# LampenSteuerung_PWM.net
KiCad netlist of a schematic drawn in EAGLE
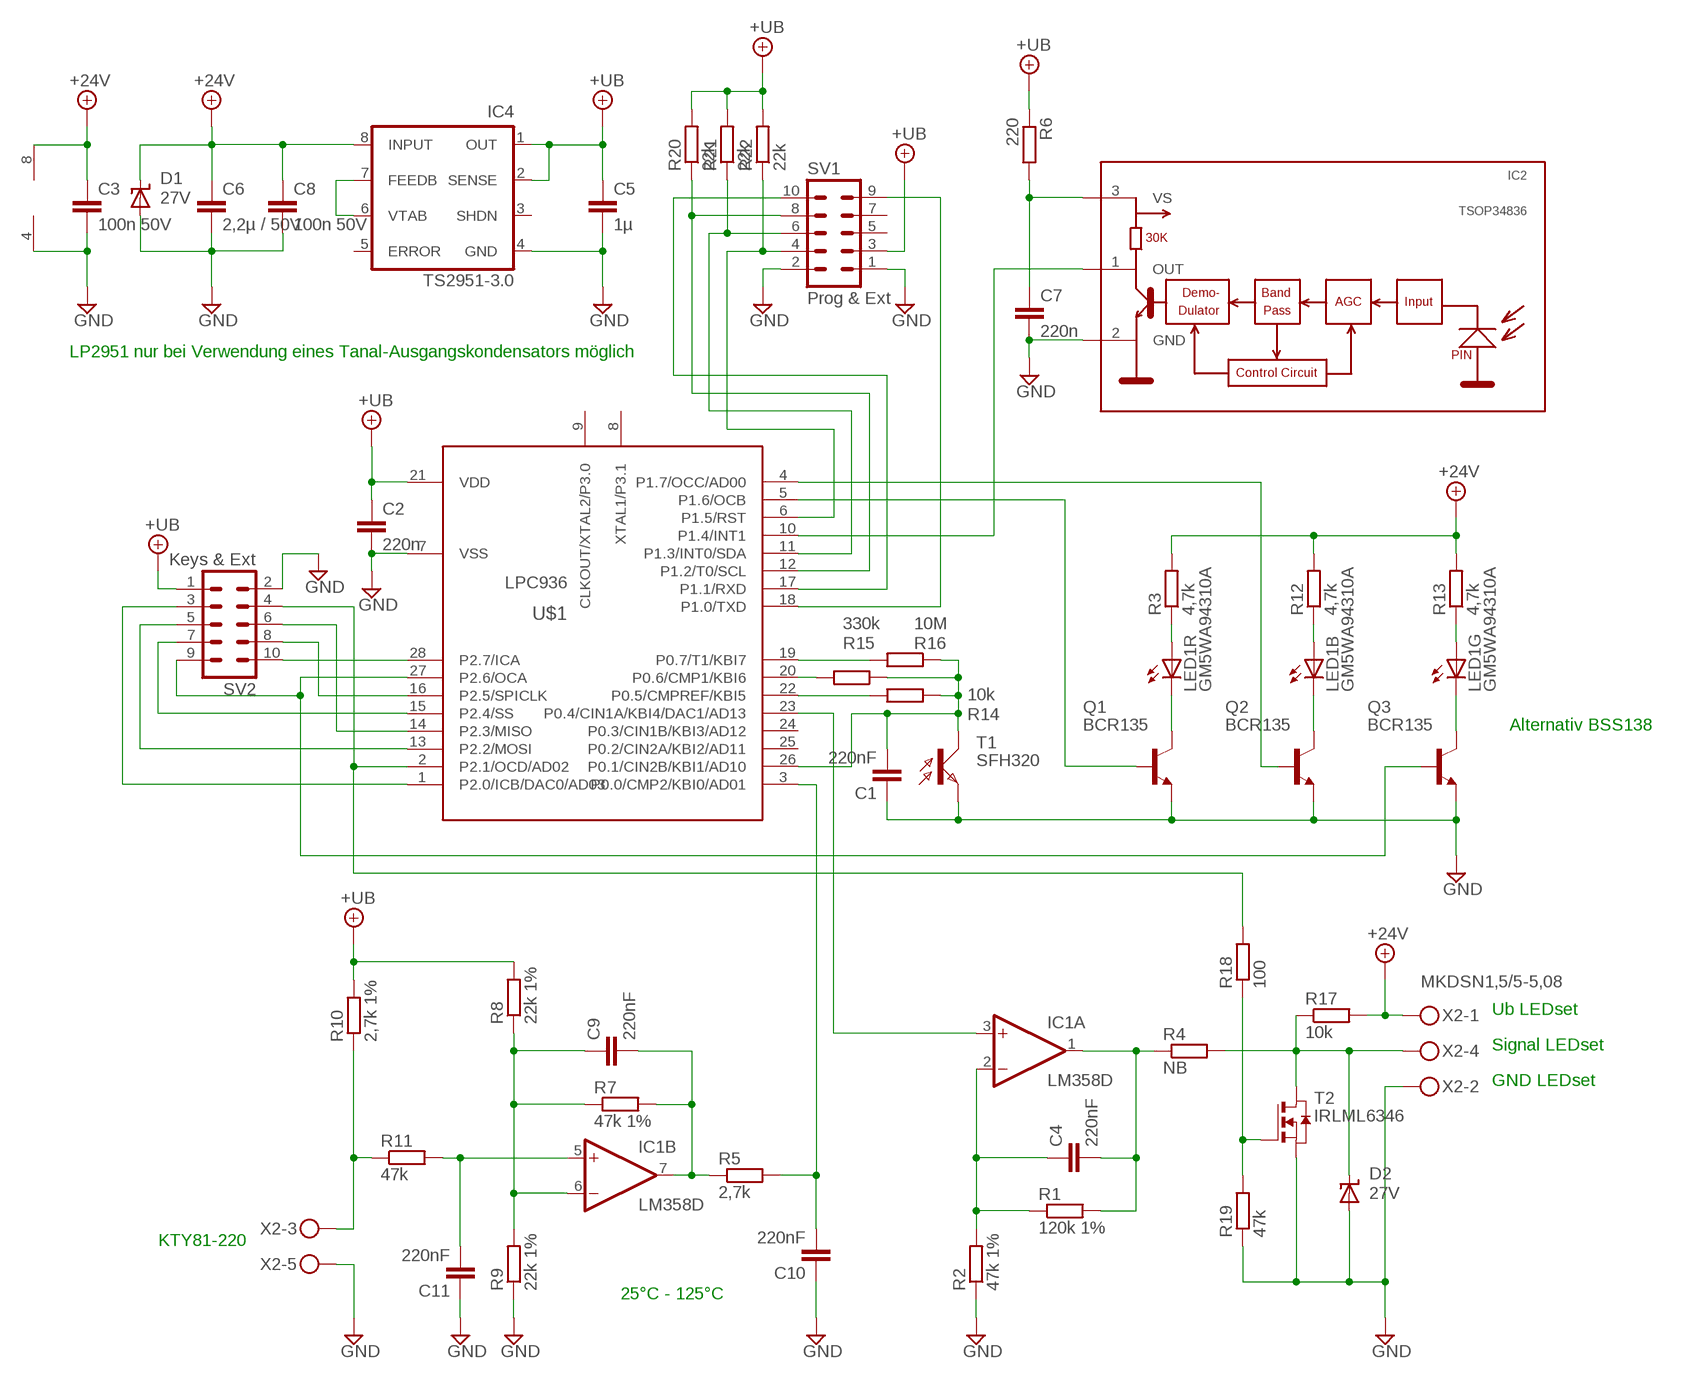
[diagram p0: schematic, sheet 1]

(export (version "E")
  (design (tool "Eeschema 10.0.6"))
  (components
    (comp (ref "C1")
      (value "220nF")
      (footprint "eagle-import:C0603")
      (libsource (lib "eagle-import") (part "C-EUC0603"))
    )
    (comp (ref "C2")
      (value "220n")
      (footprint "eagle-import:C0603")
      (libsource (lib "eagle-import") (part "C-EUC0603"))
    )
    (comp (ref "C3")
      (value "100n 50V")
      (footprint "eagle-import:C0603")
      (libsource (lib "eagle-import") (part "C-EUC0603"))
    )
    (comp (ref "C4")
      (value "220nF")
      (footprint "eagle-import:C0603")
      (libsource (lib "eagle-import") (part "C-EUC0603"))
    )
    (comp (ref "C5")
      (value "1µ")
      (footprint "eagle-import:C0805")
      (libsource (lib "eagle-import") (part "C-EUC0805"))
    )
    (comp (ref "C6")
      (value "2,2µ / 50V")
      (footprint "eagle-import:C1206")
      (libsource (lib "eagle-import") (part "C-EUC1206"))
    )
    (comp (ref "C7")
      (value "220n")
      (footprint "eagle-import:C0603")
      (libsource (lib "eagle-import") (part "C-EUC0603"))
    )
    (comp (ref "C8")
      (value "100n 50V")
      (footprint "eagle-import:C0603")
      (libsource (lib "eagle-import") (part "C-EUC0603"))
    )
    (comp (ref "C9")
      (value "220nF")
      (footprint "eagle-import:C0603")
      (libsource (lib "eagle-import") (part "C-EUC0603"))
    )
    (comp (ref "C10")
      (value "220nF")
      (footprint "eagle-import:C0603")
      (libsource (lib "eagle-import") (part "C-EUC0603"))
    )
    (comp (ref "C11")
      (value "220nF")
      (footprint "eagle-import:C0603")
      (libsource (lib "eagle-import") (part "C-EUC0603"))
    )
    (comp (ref "D1")
      (value "27V")
      (footprint "eagle-import:SMBJ")
      (libsource (lib "eagle-import") (part "SUPPRESSOR-SMBJ"))
    )
    (comp (ref "D2")
      (value "27V")
      (footprint "eagle-import:SMBJ")
      (libsource (lib "eagle-import") (part "SUPPRESSOR-SMBJ"))
    )
    (comp (ref "IC1")
      (value "LM358D")
      (footprint "eagle-import:SO08")
      (libsource (lib "eagle-import") (part "LM358D"))
    )
    (comp (ref "IC2")
      (value "TSOP34836")
      (footprint "eagle-import:TSOP348")
      (libsource (lib "eagle-import") (part "TSOP34836"))
    )
    (comp (ref "IC4")
      (value "TS2951-3.0")
      (footprint "eagle-import:SO-08")
      (libsource (lib "eagle-import") (part "LP2951?CM-3.0"))
    )
    (comp (ref "LED1")
      (value "GM5WA94310A")
      (footprint "eagle-import:GM5WA94310A")
      (libsource (lib "eagle-import") (part "GM5WA94310A"))
    )
    (comp (ref "Q1")
      (value "BCR135")
      (footprint "eagle-import:SOT23-BEC")
      (libsource (lib "eagle-import") (part "BCW60SMD"))
    )
    (comp (ref "Q2")
      (value "BCR135")
      (footprint "eagle-import:SOT23-BEC")
      (libsource (lib "eagle-import") (part "BCW60SMD"))
    )
    (comp (ref "Q3")
      (value "BCR135")
      (footprint "eagle-import:SOT23-BEC")
      (libsource (lib "eagle-import") (part "BCW60SMD"))
    )
    (comp (ref "R1")
      (value "120k 1%")
      (footprint "eagle-import:R0805")
      (libsource (lib "eagle-import") (part "R-EU_R0805"))
    )
    (comp (ref "R2")
      (value "47k 1%")
      (footprint "eagle-import:R0805")
      (libsource (lib "eagle-import") (part "R-EU_R0805"))
    )
    (comp (ref "R3")
      (value "4,7k")
      (footprint "eagle-import:R0805")
      (libsource (lib "eagle-import") (part "R-EU_R0805"))
    )
    (comp (ref "R4")
      (value "NB")
      (footprint "eagle-import:R0805")
      (libsource (lib "eagle-import") (part "R-EU_R0805"))
    )
    (comp (ref "R5")
      (value "2,7k")
      (footprint "eagle-import:R0805")
      (libsource (lib "eagle-import") (part "R-EU_R0805"))
    )
    (comp (ref "R6")
      (value "220")
      (footprint "eagle-import:R0805")
      (libsource (lib "eagle-import") (part "R-EU_R0805"))
    )
    (comp (ref "R7")
      (value "47k 1%")
      (footprint "eagle-import:R0805")
      (libsource (lib "eagle-import") (part "R-EU_R0805"))
    )
    (comp (ref "R8")
      (value "22k 1%")
      (footprint "eagle-import:R0805")
      (libsource (lib "eagle-import") (part "R-EU_R0805"))
    )
    (comp (ref "R9")
      (value "22k 1%")
      (footprint "eagle-import:R0805")
      (libsource (lib "eagle-import") (part "R-EU_R0805"))
    )
    (comp (ref "R10")
      (value "2,7k 1%")
      (footprint "eagle-import:R0805")
      (libsource (lib "eagle-import") (part "R-EU_R0805"))
    )
    (comp (ref "R11")
      (value "47k")
      (footprint "eagle-import:R0805")
      (libsource (lib "eagle-import") (part "R-EU_R0805"))
    )
    (comp (ref "R12")
      (value "4,7k")
      (footprint "eagle-import:R0805")
      (libsource (lib "eagle-import") (part "R-EU_R0805"))
    )
    (comp (ref "R13")
      (value "4,7k")
      (footprint "eagle-import:R0805")
      (libsource (lib "eagle-import") (part "R-EU_R0805"))
    )
    (comp (ref "R14")
      (value "10k")
      (footprint "eagle-import:R0805")
      (libsource (lib "eagle-import") (part "R-EU_R0805"))
    )
    (comp (ref "R15")
      (value "330k")
      (footprint "eagle-import:R0805")
      (libsource (lib "eagle-import") (part "R-EU_R0805"))
    )
    (comp (ref "R16")
      (value "10M")
      (footprint "eagle-import:R0805")
      (libsource (lib "eagle-import") (part "R-EU_R0805"))
    )
    (comp (ref "R17")
      (value "10k")
      (footprint "eagle-import:R0805")
      (libsource (lib "eagle-import") (part "R-EU_R0805"))
    )
    (comp (ref "R18")
      (value "100")
      (footprint "eagle-import:R0805")
      (libsource (lib "eagle-import") (part "R-EU_R0805"))
    )
    (comp (ref "R19")
      (value "47k")
      (footprint "eagle-import:R0805")
      (libsource (lib "eagle-import") (part "R-EU_R0805"))
    )
    (comp (ref "R20")
      (value "22k")
      (footprint "eagle-import:R0805")
      (libsource (lib "eagle-import") (part "R-EU_R0805"))
    )
    (comp (ref "R21")
      (value "22k")
      (footprint "eagle-import:R0805")
      (libsource (lib "eagle-import") (part "R-EU_R0805"))
    )
    (comp (ref "R22")
      (value "22k")
      (footprint "eagle-import:R0805")
      (libsource (lib "eagle-import") (part "R-EU_R0805"))
    )
    (comp (ref "SV1")
      (value "Prog & Ext")
      (footprint "eagle-import:MA05-2")
      (libsource (lib "eagle-import") (part "MA05-2"))
    )
    (comp (ref "SV2")
      (value "Keys & Ext")
      (footprint "eagle-import:MA05-2")
      (libsource (lib "eagle-import") (part "MA05-2"))
    )
    (comp (ref "T1")
      (value "SFH320")
      (footprint "eagle-import:PLCC2")
      (libsource (lib "eagle-import") (part "SFH320"))
    )
    (comp (ref "T2")
      (value "IRLML6346")
      (footprint "eagle-import:SOT-23")
      (libsource (lib "eagle-import") (part "NMOSSOT23"))
    )
    (comp (ref "U$1")
      (value "LPC936")
      (footprint "eagle-import:TSSOP28")
      (libsource (lib "eagle-import") (part "LPC936"))
    )
    (comp (ref "X2")
      (value "MKDSN1,5/5-5,08")
      (footprint "eagle-import:MKDSN1,5_5-5,08")
      (fields (field (name "MPN") "SMKDSN1,5/5-5,08"))
      (libsource (lib "eagle-import") (part "MKDSN1,5/5-5,08"))
    )
  )
  (nets
    (net (code "1") (name "+24V") (class "Default")
      (node (ref "C3") (pin "1") (pinfunction "1_1") (pintype "passive"))
      (node (ref "C6") (pin "1") (pinfunction "1_1") (pintype "passive"))
      (node (ref "C8") (pin "1") (pinfunction "1_1") (pintype "passive"))
      (node (ref "D1") (pin "C") (pinfunction "C_C") (pintype "passive"))
      (node (ref "IC1") (pin "8") (pinfunction "V+_8") (pintype "power_in"))
      (node (ref "IC4") (pin "8") (pinfunction "INPUT_8") (pintype "passive"))
      (node (ref "R12") (pin "2") (pinfunction "2_2") (pintype "passive"))
      (node (ref "R13") (pin "2") (pinfunction "2_2") (pintype "passive"))
      (node (ref "R17") (pin "2") (pinfunction "2_2") (pintype "passive"))
      (node (ref "R3") (pin "2") (pinfunction "2_2") (pintype "passive"))
      (node (ref "X2") (pin "1") (pinfunction "KL_1") (pintype "passive"))
    )
    (net (code "2") (name "+UB") (class "Default")
      (node (ref "C2") (pin "1") (pinfunction "1_1") (pintype "passive"))
      (node (ref "C5") (pin "1") (pinfunction "1_1") (pintype "passive"))
      (node (ref "IC4") (pin "1") (pinfunction "OUT_1") (pintype "output"))
      (node (ref "IC4") (pin "2") (pinfunction "SENSE_2") (pintype "input"))
      (node (ref "R10") (pin "2") (pinfunction "2_2") (pintype "passive"))
      (node (ref "R20") (pin "2") (pinfunction "2_2") (pintype "passive"))
      (node (ref "R21") (pin "2") (pinfunction "2_2") (pintype "passive"))
      (node (ref "R22") (pin "2") (pinfunction "2_2") (pintype "passive"))
      (node (ref "R6") (pin "1") (pinfunction "1_1") (pintype "passive"))
      (node (ref "R8") (pin "2") (pinfunction "2_2") (pintype "passive"))
      (node (ref "SV1") (pin "3") (pinfunction "3_3") (pintype "passive"))
      (node (ref "SV2") (pin "1") (pinfunction "1_1") (pintype "passive"))
      (node (ref "U$1") (pin "21") (pinfunction "VDD_21") (pintype "bidirectional"))
    )
    (net (code "3") (name "GND") (class "Default")
      (node (ref "C1") (pin "1") (pinfunction "1_1") (pintype "passive"))
      (node (ref "C10") (pin "1") (pinfunction "1_1") (pintype "passive"))
      (node (ref "C11") (pin "1") (pinfunction "1_1") (pintype "passive"))
      (node (ref "C2") (pin "2") (pinfunction "2_2") (pintype "passive"))
      (node (ref "C3") (pin "2") (pinfunction "2_2") (pintype "passive"))
      (node (ref "C5") (pin "2") (pinfunction "2_2") (pintype "passive"))
      (node (ref "C6") (pin "2") (pinfunction "2_2") (pintype "passive"))
      (node (ref "C7") (pin "2") (pinfunction "2_2") (pintype "passive"))
      (node (ref "C8") (pin "2") (pinfunction "2_2") (pintype "passive"))
      (node (ref "D1") (pin "A") (pinfunction "A_A") (pintype "passive"))
      (node (ref "D2") (pin "A") (pinfunction "A_A") (pintype "passive"))
      (node (ref "IC1") (pin "4") (pinfunction "V-_4") (pintype "power_in"))
      (node (ref "IC2") (pin "2") (pinfunction "GND_2") (pintype "power_in"))
      (node (ref "IC4") (pin "4") (pinfunction "GND_4") (pintype "power_in"))
      (node (ref "Q1") (pin "E") (pinfunction "E_E") (pintype "passive"))
      (node (ref "Q2") (pin "E") (pinfunction "E_E") (pintype "passive"))
      (node (ref "Q3") (pin "E") (pinfunction "E_E") (pintype "passive"))
      (node (ref "R19") (pin "1") (pinfunction "1_1") (pintype "passive"))
      (node (ref "R2") (pin "1") (pinfunction "1_1") (pintype "passive"))
      (node (ref "R9") (pin "1") (pinfunction "1_1") (pintype "passive"))
      (node (ref "SV1") (pin "1") (pinfunction "1_1") (pintype "passive"))
      (node (ref "SV1") (pin "2") (pinfunction "2_2") (pintype "passive"))
      (node (ref "SV2") (pin "2") (pinfunction "2_2") (pintype "passive"))
      (node (ref "T1") (pin "C") (pinfunction "E_C") (pintype "passive"))
      (node (ref "T2") (pin "2") (pinfunction "S_2") (pintype "passive"))
      (node (ref "U$1") (pin "7") (pinfunction "VSS_7") (pintype "bidirectional"))
      (node (ref "X2") (pin "2") (pinfunction "KL_2") (pintype "passive"))
      (node (ref "X2") (pin "5") (pinfunction "KL_5") (pintype "passive"))
    )
    (net (code "4") (name "Net-(IC1A-+IN)") (class "Default")
      (node (ref "IC1") (pin "3") (pinfunction "+IN_3") (pintype "input"))
      (node (ref "U$1") (pin "23") (pinfunction "P0.4/CIN1A/KBI4/DAC1/AD13_23") (pintype "bidirectional"))
    )
    (net (code "5") (name "Net-(IC1A--IN)") (class "Default")
      (node (ref "C4") (pin "1") (pinfunction "1_1") (pintype "passive"))
      (node (ref "IC1") (pin "2") (pinfunction "-IN_2") (pintype "input"))
      (node (ref "R1") (pin "1") (pinfunction "1_1") (pintype "passive"))
      (node (ref "R2") (pin "2") (pinfunction "2_2") (pintype "passive"))
    )
    (net (code "6") (name "Net-(IC1A-OUT)") (class "Default")
      (node (ref "C4") (pin "2") (pinfunction "2_2") (pintype "passive"))
      (node (ref "IC1") (pin "1") (pinfunction "OUT_1") (pintype "output"))
      (node (ref "R1") (pin "2") (pinfunction "2_2") (pintype "passive"))
      (node (ref "R4") (pin "1") (pinfunction "1_1") (pintype "passive"))
    )
    (net (code "7") (name "Net-(IC1B-+IN)") (class "Default")
      (node (ref "C11") (pin "2") (pinfunction "2_2") (pintype "passive"))
      (node (ref "IC1") (pin "5") (pinfunction "+IN_5") (pintype "input"))
      (node (ref "R11") (pin "2") (pinfunction "2_2") (pintype "passive"))
    )
    (net (code "8") (name "Net-(IC1B--IN)") (class "Default")
      (node (ref "C9") (pin "1") (pinfunction "1_1") (pintype "passive"))
      (node (ref "IC1") (pin "6") (pinfunction "-IN_6") (pintype "input"))
      (node (ref "R7") (pin "1") (pinfunction "1_1") (pintype "passive"))
      (node (ref "R8") (pin "1") (pinfunction "1_1") (pintype "passive"))
      (node (ref "R9") (pin "2") (pinfunction "2_2") (pintype "passive"))
    )
    (net (code "9") (name "Net-(IC1B-OUT)") (class "Default")
      (node (ref "C9") (pin "2") (pinfunction "2_2") (pintype "passive"))
      (node (ref "IC1") (pin "7") (pinfunction "OUT_7") (pintype "output"))
      (node (ref "R5") (pin "1") (pinfunction "1_1") (pintype "passive"))
      (node (ref "R7") (pin "2") (pinfunction "2_2") (pintype "passive"))
    )
    (net (code "10") (name "Net-(IC2-OUT)") (class "Default")
      (node (ref "IC2") (pin "1") (pinfunction "OUT_1") (pintype "output"))
      (node (ref "U$1") (pin "10") (pinfunction "P1.4/INT1_10") (pintype "bidirectional"))
    )
    (net (code "11") (name "Net-(IC2-VS)") (class "Default")
      (node (ref "C7") (pin "1") (pinfunction "1_1") (pintype "passive"))
      (node (ref "IC2") (pin "3") (pinfunction "VS_3") (pintype "power_in"))
      (node (ref "R6") (pin "2") (pinfunction "2_2") (pintype "passive"))
    )
    (net (code "12") (name "Net-(IC4-FEEDB)") (class "Default")
      (node (ref "IC4") (pin "6") (pinfunction "VTAB_6") (pintype "input"))
      (node (ref "IC4") (pin "7") (pinfunction "FEEDB_7") (pintype "output"))
    )
    (net (code "13") (name "Net-(LED1A-A)") (class "Default")
      (node (ref "LED1") (pin "1") (pinfunction "A_1") (pintype "passive"))
      (node (ref "R12") (pin "1") (pinfunction "1_1") (pintype "passive"))
    )
    (net (code "14") (name "Net-(LED1A-C)") (class "Default")
      (node (ref "LED1") (pin "6") (pinfunction "C_6") (pintype "passive"))
      (node (ref "Q2") (pin "C") (pinfunction "C_C") (pintype "passive"))
    )
    (net (code "15") (name "Net-(LED1B-A)") (class "Default")
      (node (ref "LED1") (pin "3") (pinfunction "A_3") (pintype "passive"))
      (node (ref "R13") (pin "1") (pinfunction "1_1") (pintype "passive"))
    )
    (net (code "16") (name "Net-(LED1B-C)") (class "Default")
      (node (ref "LED1") (pin "4") (pinfunction "C_4") (pintype "passive"))
      (node (ref "Q3") (pin "C") (pinfunction "C_C") (pintype "passive"))
    )
    (net (code "17") (name "Net-(LED1C-A)") (class "Default")
      (node (ref "LED1") (pin "2") (pinfunction "A_2") (pintype "passive"))
      (node (ref "R3") (pin "1") (pinfunction "1_1") (pintype "passive"))
    )
    (net (code "18") (name "Net-(LED1C-C)") (class "Default")
      (node (ref "LED1") (pin "5") (pinfunction "C_5") (pintype "passive"))
      (node (ref "Q1") (pin "C") (pinfunction "C_C") (pintype "passive"))
    )
    (net (code "19") (name "Net-(T1-C)") (class "Default")
      (node (ref "C1") (pin "2") (pinfunction "2_2") (pintype "passive"))
      (node (ref "R14") (pin "1") (pinfunction "1_1") (pintype "passive"))
      (node (ref "R15") (pin "1") (pinfunction "1_1") (pintype "passive"))
      (node (ref "R16") (pin "1") (pinfunction "1_1") (pintype "passive"))
      (node (ref "T1") (pin "A") (pinfunction "C_A") (pintype "passive"))
      (node (ref "U$1") (pin "26") (pinfunction "P0.1/CIN2B/KBI1/AD10_26") (pintype "bidirectional"))
    )
    (net (code "20") (name "Net-(T2-D)") (class "Default")
      (node (ref "D2") (pin "C") (pinfunction "C_C") (pintype "passive"))
      (node (ref "R17") (pin "1") (pinfunction "1_1") (pintype "passive"))
      (node (ref "R4") (pin "2") (pinfunction "2_2") (pintype "passive"))
      (node (ref "T2") (pin "1") (pinfunction "D_1") (pintype "passive"))
      (node (ref "X2") (pin "4") (pinfunction "KL_4") (pintype "passive"))
    )
    (net (code "21") (name "Net-(T2-G)") (class "Default")
      (node (ref "R18") (pin "1") (pinfunction "1_1") (pintype "passive"))
      (node (ref "R19") (pin "2") (pinfunction "2_2") (pintype "passive"))
      (node (ref "T2") (pin "3") (pinfunction "G_3") (pintype "passive"))
    )
    (net (code "22") (name "Net-(U$1-P0.0{slash}CMP2{slash}KBI0{slash}AD01)") (class "Default")
      (node (ref "C10") (pin "2") (pinfunction "2_2") (pintype "passive"))
      (node (ref "R5") (pin "2") (pinfunction "2_2") (pintype "passive"))
      (node (ref "U$1") (pin "3") (pinfunction "P0.0/CMP2/KBI0/AD01_3") (pintype "bidirectional"))
    )
    (net (code "23") (name "Net-(U$1-P0.5{slash}CMPREF{slash}KBI5)") (class "Default")
      (node (ref "R14") (pin "2") (pinfunction "2_2") (pintype "passive"))
      (node (ref "U$1") (pin "22") (pinfunction "P0.5/CMPREF/KBI5_22") (pintype "bidirectional"))
    )
    (net (code "24") (name "Net-(U$1-P0.6{slash}CMP1{slash}KBI6)") (class "Default")
      (node (ref "R15") (pin "2") (pinfunction "2_2") (pintype "passive"))
      (node (ref "U$1") (pin "20") (pinfunction "P0.6/CMP1/KBI6_20") (pintype "bidirectional"))
    )
    (net (code "25") (name "Net-(U$1-P0.7{slash}T1{slash}KBI7)") (class "Default")
      (node (ref "R16") (pin "2") (pinfunction "2_2") (pintype "passive"))
      (node (ref "U$1") (pin "19") (pinfunction "P0.7/T1/KBI7_19") (pintype "bidirectional"))
    )
    (net (code "26") (name "Net-(U$1-P1.0{slash}TXD)") (class "Default")
      (node (ref "SV1") (pin "9") (pinfunction "9_9") (pintype "passive"))
      (node (ref "U$1") (pin "18") (pinfunction "P1.0/TXD_18") (pintype "bidirectional"))
    )
    (net (code "27") (name "Net-(U$1-P1.1{slash}RXD)") (class "Default")
      (node (ref "SV1") (pin "10") (pinfunction "10_10") (pintype "passive"))
      (node (ref "U$1") (pin "17") (pinfunction "P1.1/RXD_17") (pintype "bidirectional"))
    )
    (net (code "28") (name "Net-(U$1-P1.2{slash}T0{slash}SCL)") (class "Default")
      (node (ref "R20") (pin "1") (pinfunction "1_1") (pintype "passive"))
      (node (ref "SV1") (pin "8") (pinfunction "8_8") (pintype "passive"))
      (node (ref "U$1") (pin "12") (pinfunction "P1.2/T0/SCL_12") (pintype "bidirectional"))
    )
    (net (code "29") (name "Net-(U$1-P1.3{slash}INT0{slash}SDA)") (class "Default")
      (node (ref "R21") (pin "1") (pinfunction "1_1") (pintype "passive"))
      (node (ref "SV1") (pin "6") (pinfunction "6_6") (pintype "passive"))
      (node (ref "U$1") (pin "11") (pinfunction "P1.3/INT0/SDA_11") (pintype "bidirectional"))
    )
    (net (code "30") (name "Net-(U$1-P1.5{slash}RST)") (class "Default")
      (node (ref "R22") (pin "1") (pinfunction "1_1") (pintype "passive"))
      (node (ref "SV1") (pin "4") (pinfunction "4_4") (pintype "passive"))
      (node (ref "U$1") (pin "6") (pinfunction "P1.5/RST_6") (pintype "bidirectional"))
    )
    (net (code "31") (name "Net-(U$1-P1.6{slash}OCB)") (class "Default")
      (node (ref "Q1") (pin "B") (pinfunction "B_B") (pintype "passive"))
      (node (ref "U$1") (pin "5") (pinfunction "P1.6/OCB_5") (pintype "bidirectional"))
    )
    (net (code "32") (name "Net-(U$1-P1.7{slash}OCC{slash}AD00)") (class "Default")
      (node (ref "Q2") (pin "B") (pinfunction "B_B") (pintype "passive"))
      (node (ref "U$1") (pin "4") (pinfunction "P1.7/OCC/AD00_4") (pintype "bidirectional"))
    )
    (net (code "33") (name "Net-(U$1-P2.0{slash}ICB{slash}DAC0{slash}AD03)") (class "Default")
      (node (ref "SV2") (pin "3") (pinfunction "3_3") (pintype "passive"))
      (node (ref "U$1") (pin "1") (pinfunction "P2.0/ICB/DAC0/AD03_1") (pintype "bidirectional"))
    )
    (net (code "34") (name "Net-(U$1-P2.1{slash}OCD{slash}AD02)") (class "Default")
      (node (ref "R18") (pin "2") (pinfunction "2_2") (pintype "passive"))
      (node (ref "SV2") (pin "4") (pinfunction "4_4") (pintype "passive"))
      (node (ref "U$1") (pin "2") (pinfunction "P2.1/OCD/AD02_2") (pintype "bidirectional"))
    )
    (net (code "35") (name "Net-(U$1-P2.2{slash}MOSI)") (class "Default")
      (node (ref "SV2") (pin "5") (pinfunction "5_5") (pintype "passive"))
      (node (ref "U$1") (pin "13") (pinfunction "P2.2/MOSI_13") (pintype "bidirectional"))
    )
    (net (code "36") (name "Net-(U$1-P2.3{slash}MISO)") (class "Default")
      (node (ref "SV2") (pin "6") (pinfunction "6_6") (pintype "passive"))
      (node (ref "U$1") (pin "14") (pinfunction "P2.3/MISO_14") (pintype "bidirectional"))
    )
    (net (code "37") (name "Net-(U$1-P2.4{slash}SS)") (class "Default")
      (node (ref "SV2") (pin "7") (pinfunction "7_7") (pintype "passive"))
      (node (ref "U$1") (pin "15") (pinfunction "P2.4/SS_15") (pintype "bidirectional"))
    )
    (net (code "38") (name "Net-(U$1-P2.5{slash}SPICLK)") (class "Default")
      (node (ref "SV2") (pin "8") (pinfunction "8_8") (pintype "passive"))
      (node (ref "U$1") (pin "16") (pinfunction "P2.5/SPICLK_16") (pintype "bidirectional"))
    )
    (net (code "39") (name "Net-(U$1-P2.6{slash}OCA)") (class "Default")
      (node (ref "Q3") (pin "B") (pinfunction "B_B") (pintype "passive"))
      (node (ref "SV2") (pin "9") (pinfunction "9_9") (pintype "passive"))
      (node (ref "U$1") (pin "27") (pinfunction "P2.6/OCA_27") (pintype "bidirectional"))
    )
    (net (code "40") (name "Net-(U$1-P2.7{slash}ICA)") (class "Default")
      (node (ref "SV2") (pin "10") (pinfunction "10_10") (pintype "passive"))
      (node (ref "U$1") (pin "28") (pinfunction "P2.7/ICA_28") (pintype "bidirectional"))
    )
    (net (code "41") (name "Net-(X2C-KL)") (class "Default")
      (node (ref "R10") (pin "1") (pinfunction "1_1") (pintype "passive"))
      (node (ref "R11") (pin "1") (pinfunction "1_1") (pintype "passive"))
      (node (ref "X2") (pin "3") (pinfunction "KL_3") (pintype "passive"))
    )
    (net (code "42") (name "unconnected-(IC4-ERROR-Pad5)") (class "Default")
      (node (ref "IC4") (pin "5") (pinfunction "ERROR_5") (pintype "output"))
    )
    (net (code "43") (name "unconnected-(IC4-SHDN-Pad3)") (class "Default")
      (node (ref "IC4") (pin "3") (pinfunction "SHDN_3") (pintype "input"))
    )
    (net (code "44") (name "unconnected-(SV1-Pad5)") (class "Default")
      (node (ref "SV1") (pin "5") (pinfunction "5_5") (pintype "passive"))
    )
    (net (code "45") (name "unconnected-(SV1-Pad7)") (class "Default")
      (node (ref "SV1") (pin "7") (pinfunction "7_7") (pintype "passive"))
    )
    (net (code "46") (name "unconnected-(U$1-CLKOUT{slash}XTAL2{slash}P3.0-Pad9)") (class "Default")
      (node (ref "U$1") (pin "9") (pinfunction "CLKOUT/XTAL2/P3.0_9") (pintype "bidirectional"))
    )
    (net (code "47") (name "unconnected-(U$1-P0.2{slash}CIN2A{slash}KBI2{slash}AD11-Pad25)") (class "Default")
      (node (ref "U$1") (pin "25") (pinfunction "P0.2/CIN2A/KBI2/AD11_25") (pintype "bidirectional"))
    )
    (net (code "48") (name "unconnected-(U$1-P0.3{slash}CIN1B{slash}KBI3{slash}AD12-Pad24)") (class "Default")
      (node (ref "U$1") (pin "24") (pinfunction "P0.3/CIN1B/KBI3/AD12_24") (pintype "bidirectional"))
    )
    (net (code "49") (name "unconnected-(U$1-XTAL1{slash}P3.1-Pad8)") (class "Default")
      (node (ref "U$1") (pin "8") (pinfunction "XTAL1/P3.1_8") (pintype "bidirectional"))
    )
  )
)
